# attiny85.net
KiCad netlist of a schematic drawn in EAGLE
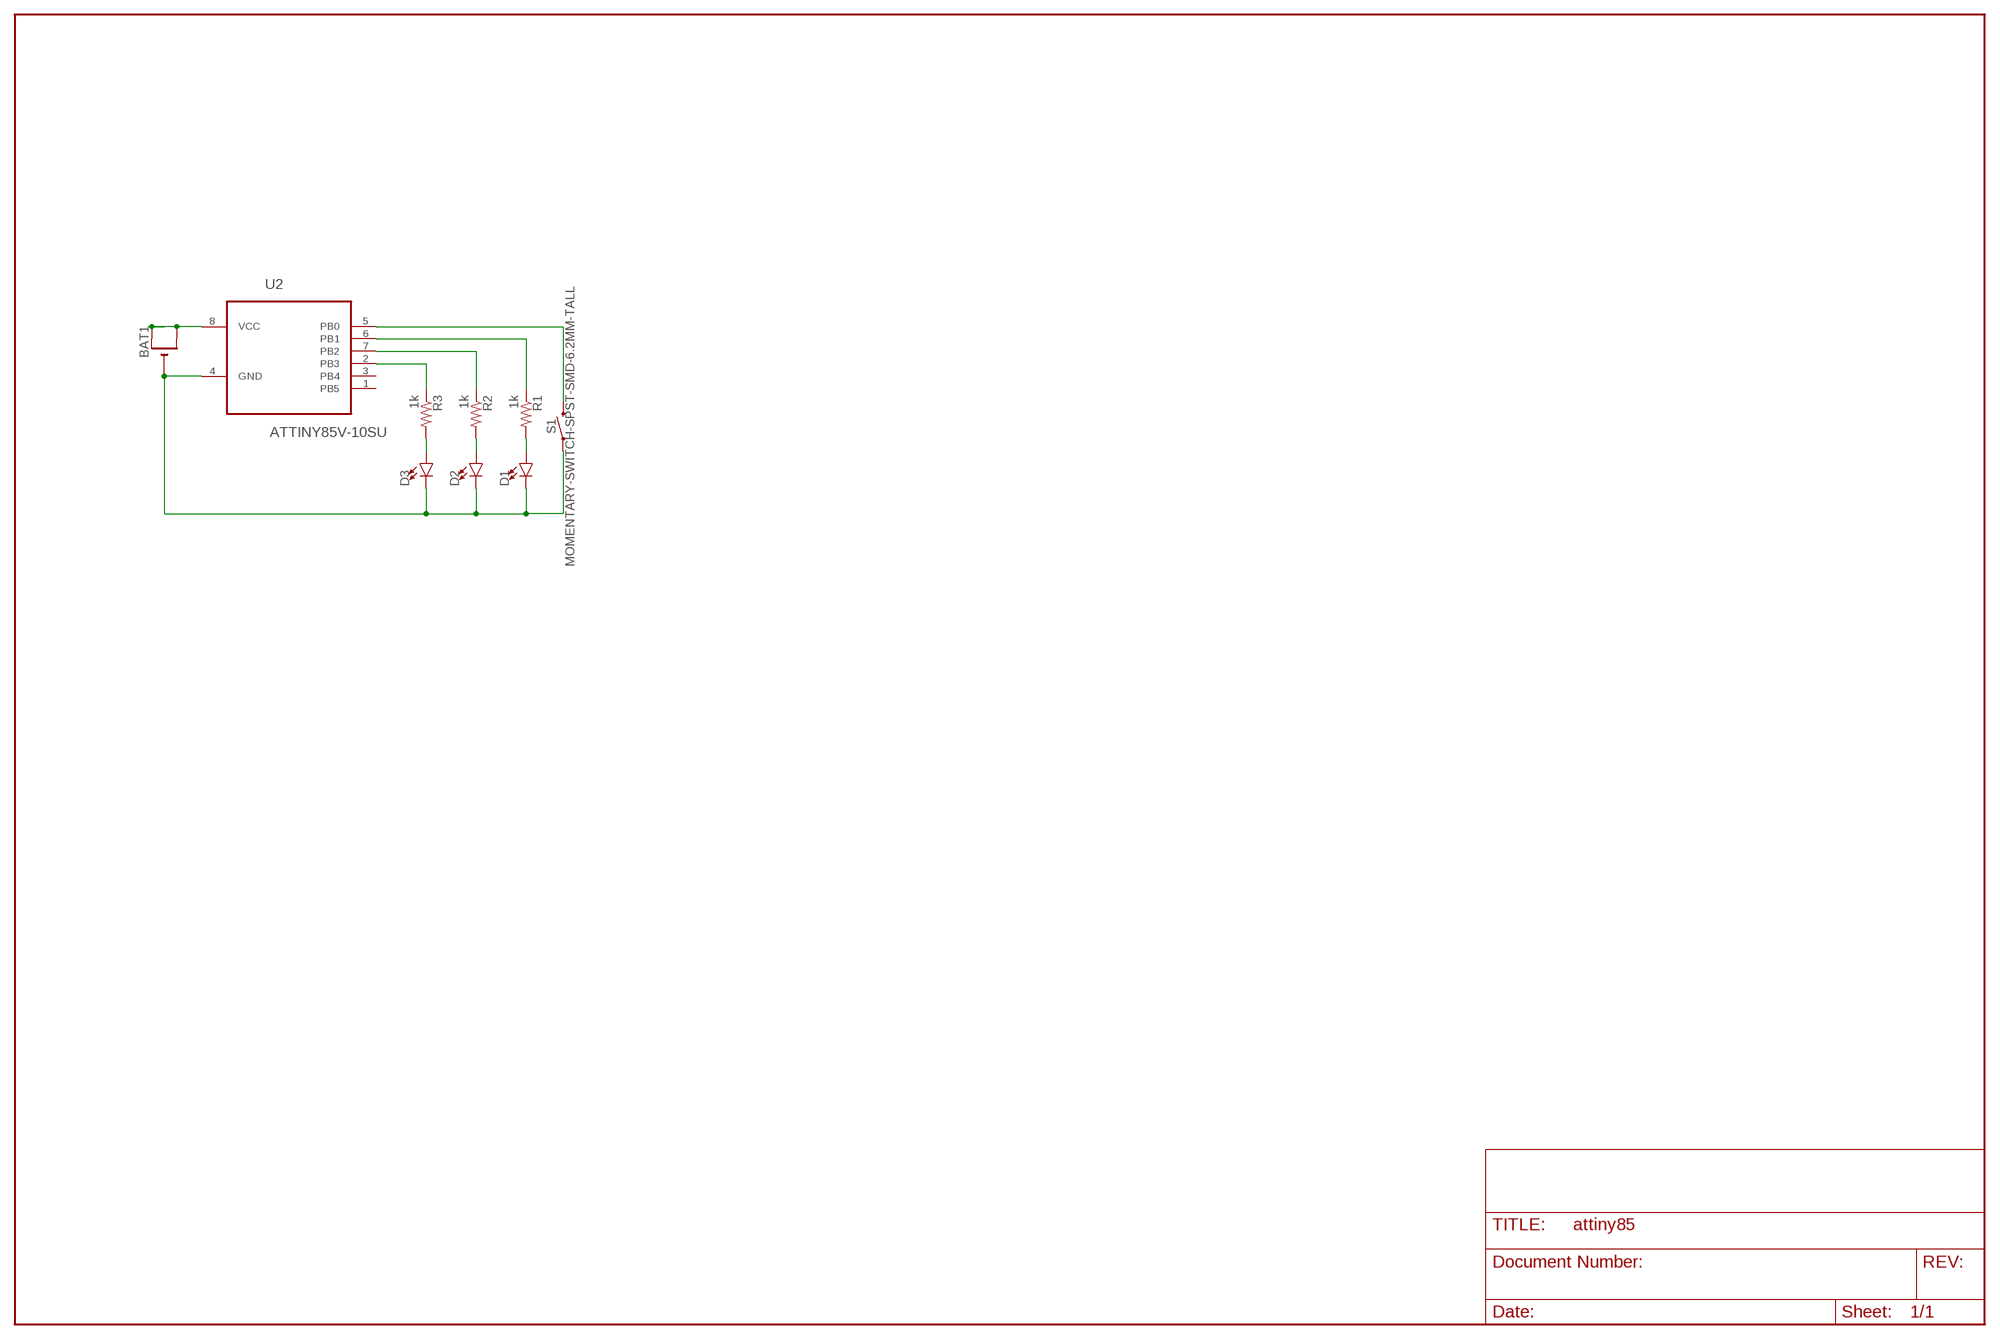
[diagram p0: schematic, sheet 1]

(export (version "E")
  (design (tool "Eeschema 10.0.6"))
  (components
    (comp (ref "BAT1")
      (value "CR2032SMT")
      (footprint "eagle-import:CR2032-SMD")
      (libsource (lib "eagle-import") (part "CR2032SMT"))
    )
    (comp (ref "D1")
      (value "LED1206")
      (footprint "eagle-import:LED-1206")
      (libsource (lib "eagle-import") (part "LED1206"))
    )
    (comp (ref "D2")
      (value "LED1206")
      (footprint "eagle-import:LED-1206")
      (libsource (lib "eagle-import") (part "LED1206"))
    )
    (comp (ref "D3")
      (value "LED1206")
      (footprint "eagle-import:LED-1206")
      (libsource (lib "eagle-import") (part "LED1206"))
    )
    (comp (ref "R1")
      (value "1k")
      (footprint "eagle-import:M1206")
      (libsource (lib "eagle-import") (part "R-US_M1206"))
    )
    (comp (ref "R2")
      (value "1k")
      (footprint "eagle-import:M1206")
      (libsource (lib "eagle-import") (part "R-US_M1206"))
    )
    (comp (ref "R3")
      (value "1k")
      (footprint "eagle-import:M1206")
      (libsource (lib "eagle-import") (part "R-US_M1206"))
    )
    (comp (ref "S1")
      (value "MOMENTARY-SWITCH-SPST-SMD-6.2MM-TALL")
      (footprint "eagle-import:TACTILE_SWITCH_SMD_6.2MM_TALL")
      (libsource (lib "eagle-import") (part "MOMENTARY-SWITCH-SPST-SMD-6.2MM-TALL"))
    )
    (comp (ref "U2")
      (value "ATTINY85V-10SU")
      (footprint "eagle-import:SOIC127P798X216-8N")
      (libsource (lib "eagle-import") (part "ATTINY85V-10SU"))
    )
  )
  (nets
    (net (code "1") (name "Net-(BAT1-+)") (class "Default")
      (node (ref "BAT1") (pin "+$1") (pinfunction "+_+$1") (pintype "passive"))
      (node (ref "BAT1") (pin "+$2") (pinfunction "+1_+$2") (pintype "passive"))
      (node (ref "U2") (pin "8") (pinfunction "VCC_8") (pintype "power_in"))
    )
    (net (code "2") (name "Net-(D1-PadA)") (class "Default")
      (node (ref "D1") (pin "A") (pinfunction "A_A") (pintype "passive"))
      (node (ref "R1") (pin "2") (pinfunction "2_2") (pintype "passive"))
    )
    (net (code "3") (name "Net-(D2-PadA)") (class "Default")
      (node (ref "D2") (pin "A") (pinfunction "A_A") (pintype "passive"))
      (node (ref "R2") (pin "2") (pinfunction "2_2") (pintype "passive"))
    )
    (net (code "4") (name "Net-(D3-PadA)") (class "Default")
      (node (ref "D3") (pin "A") (pinfunction "A_A") (pintype "passive"))
      (node (ref "R3") (pin "2") (pinfunction "2_2") (pintype "passive"))
    )
    (net (code "5") (name "Net-(S1-1)") (class "Default")
      (node (ref "BAT1") (pin "-") (pinfunction "-_-") (pintype "passive"))
      (node (ref "D1") (pin "C") (pinfunction "C_C") (pintype "passive"))
      (node (ref "D2") (pin "C") (pinfunction "C_C") (pintype "passive"))
      (node (ref "D3") (pin "C") (pinfunction "C_C") (pintype "passive"))
      (node (ref "S1") (pin "A2") (pinfunction "1_A2") (pintype "passive"))
      (node (ref "U2") (pin "4") (pinfunction "GND_4") (pintype "passive"))
    )
    (net (code "6") (name "Net-(S1-2)") (class "Default")
      (node (ref "S1") (pin "B2") (pinfunction "2_B2") (pintype "passive"))
      (node (ref "U2") (pin "5") (pinfunction "PB0_5") (pintype "bidirectional"))
    )
    (net (code "7") (name "Net-(U2-PB1)") (class "Default")
      (node (ref "R1") (pin "1") (pinfunction "1_1") (pintype "passive"))
      (node (ref "U2") (pin "6") (pinfunction "PB1_6") (pintype "bidirectional"))
    )
    (net (code "8") (name "Net-(U2-PB2)") (class "Default")
      (node (ref "R2") (pin "1") (pinfunction "1_1") (pintype "passive"))
      (node (ref "U2") (pin "7") (pinfunction "PB2_7") (pintype "bidirectional"))
    )
    (net (code "9") (name "Net-(U2-PB3)") (class "Default")
      (node (ref "R3") (pin "1") (pinfunction "1_1") (pintype "passive"))
      (node (ref "U2") (pin "2") (pinfunction "PB3_2") (pintype "bidirectional"))
    )
    (net (code "10") (name "unconnected-(U2-PB4-Pad3)") (class "Default")
      (node (ref "U2") (pin "3") (pinfunction "PB4_3") (pintype "bidirectional"))
    )
    (net (code "11") (name "unconnected-(U2-PB5-Pad1)") (class "Default")
      (node (ref "U2") (pin "1") (pinfunction "PB5_1") (pintype "bidirectional"))
    )
  )
)
